# nuc5v1.net
KiCad netlist of a schematic drawn in Altium Designer
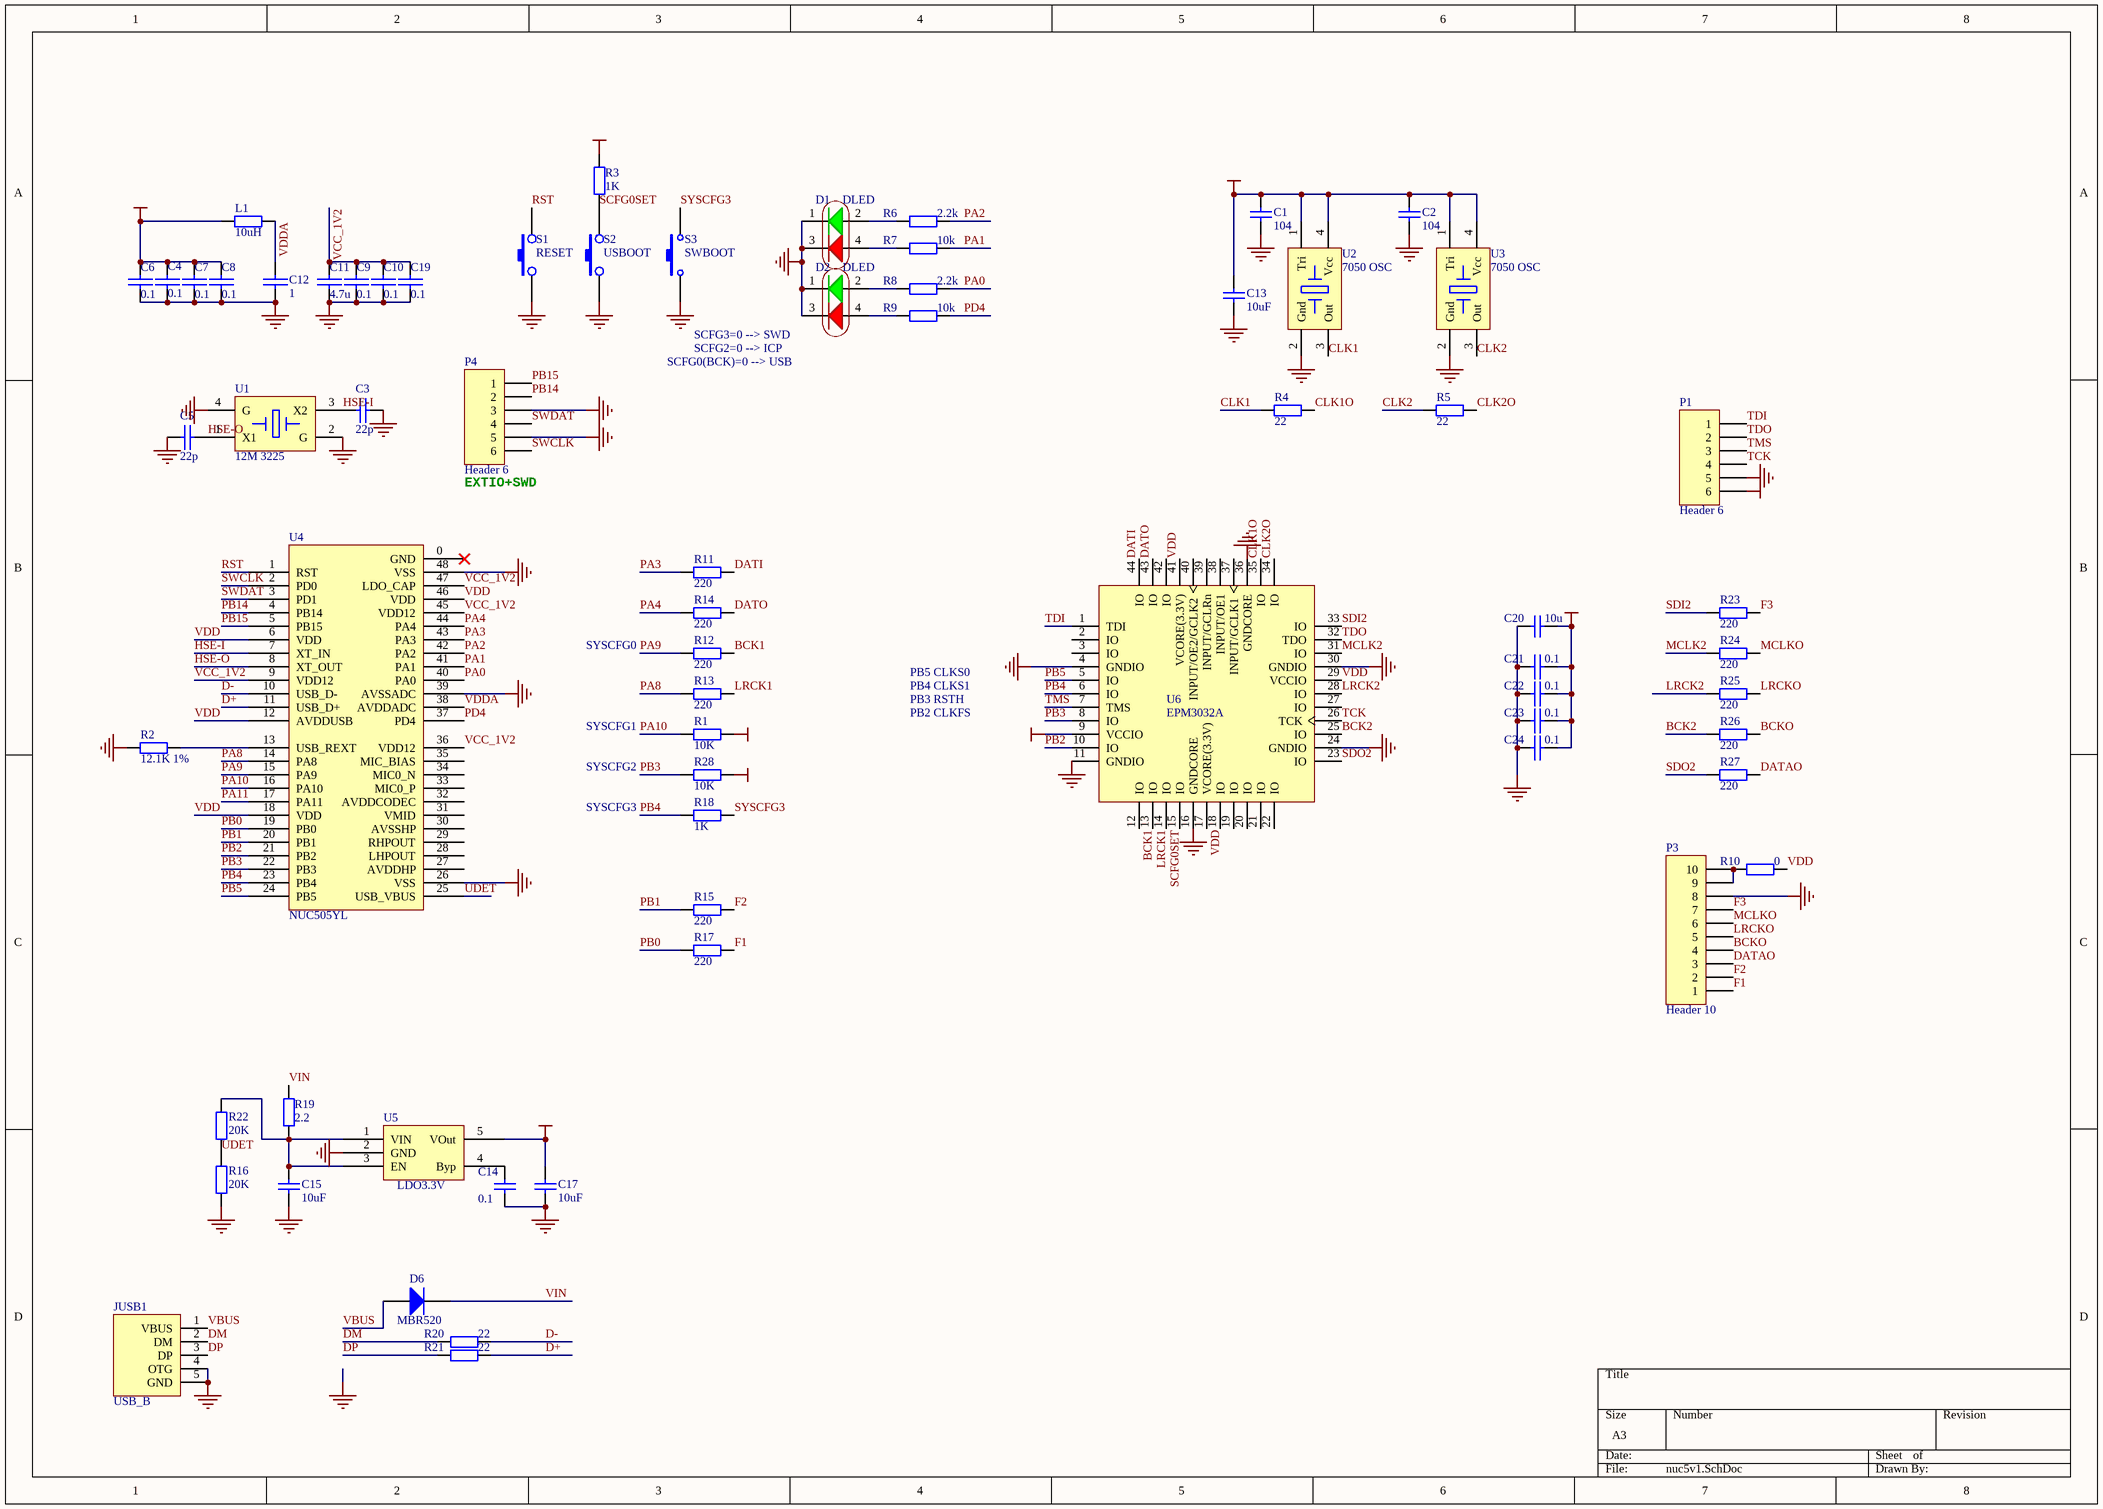
[diagram p0: nuc5v1.SchDoc]

(export (version "E")
  (design (tool "Eeschema 10.0.6"))
  (components
    (comp (ref "C1")
      (value "104")
      (footprint "CC0603CAP")
      (description "Capacitor0603")
      (libsource (lib "ADI1955-Sch") (part "Cap6"))
    )
    (comp (ref "C2")
      (value "104")
      (footprint "CC0603CAP")
      (description "Capacitor0603")
      (libsource (lib "ADI1955-Sch") (part "Cap6"))
    )
    (comp (ref "C3")
      (value "22p")
      (footprint "0603")
      (description "Capacitor")
      (libsource (lib "*") (part "CAP"))
    )
    (comp (ref "C4")
      (value "0.1")
      (footprint "0603")
      (description "Capacitor")
      (libsource (lib "*") (part "CAP"))
    )
    (comp (ref "C5")
      (value "22p")
      (footprint "0603")
      (description "Capacitor")
      (libsource (lib "") (part "CAP_1"))
    )
    (comp (ref "C6")
      (value "0.1")
      (footprint "0603")
      (description "Capacitor")
      (libsource (lib "*") (part "CAP"))
    )
    (comp (ref "C7")
      (value "0.1")
      (footprint "0603")
      (description "Capacitor")
      (libsource (lib "*") (part "CAP"))
    )
    (comp (ref "C8")
      (value "0.1")
      (footprint "0603")
      (description "Capacitor")
      (libsource (lib "*") (part "CAP"))
    )
    (comp (ref "C9")
      (value "0.1")
      (footprint "0603")
      (description "Capacitor")
      (libsource (lib "*") (part "CAP"))
    )
    (comp (ref "C10")
      (value "0.1")
      (footprint "0603")
      (description "Capacitor")
      (libsource (lib "*") (part "CAP"))
    )
    (comp (ref "C11")
      (value "4.7u")
      (footprint "0603")
      (description "Capacitor")
      (libsource (lib "*") (part "CAP"))
    )
    (comp (ref "C12")
      (value "1")
      (footprint "0603")
      (description "Capacitor")
      (libsource (lib "*") (part "CAP"))
    )
    (comp (ref "C13")
      (value "10uF")
      (footprint "CC0805CAP")
      (description "Capacitor0805")
      (libsource (lib "AudioLCR") (part "Cap8"))
    )
    (comp (ref "C14")
      (value "0.1")
      (footprint "0603")
      (description "Capacitor0805")
      (libsource (lib "*") (part "Cap8"))
    )
    (comp (ref "C15")
      (value "10uF")
      (footprint "CC0805CAP")
      (description "Capacitor0805")
      (libsource (lib "AudioLCR") (part "Cap8"))
    )
    (comp (ref "C17")
      (value "10uF")
      (footprint "CC0805CAP")
      (description "Capacitor0805")
      (libsource (lib "AudioLCR") (part "Cap8"))
    )
    (comp (ref "C19")
      (value "0.1")
      (footprint "0603")
      (description "Capacitor")
      (libsource (lib "*") (part "CAP"))
    )
    (comp (ref "C20")
      (value "10u")
      (footprint "CC0805CAP")
      (description "Capacitor0805")
      (libsource (lib "S1-LCR") (part "Cap8"))
    )
    (comp (ref "C21")
      (value "0.1")
      (footprint "0603")
      (description "Capacitor")
      (libsource (lib "*") (part "CAP"))
    )
    (comp (ref "C22")
      (value "0.1")
      (footprint "0603")
      (description "Capacitor")
      (libsource (lib "*") (part "CAP"))
    )
    (comp (ref "C23")
      (value "0.1")
      (footprint "0603")
      (description "Capacitor")
      (libsource (lib "*") (part "CAP"))
    )
    (comp (ref "C24")
      (value "0.1")
      (footprint "0603")
      (description "Capacitor")
      (libsource (lib "*") (part "CAP"))
    )
    (comp (ref "D1")
      (value "DLED")
      (footprint "LED1204")
      (description "1204双色LED")
      (libsource (lib "S1-常用") (part "LED1204"))
    )
    (comp (ref "D2")
      (value "DLED")
      (footprint "LED1204")
      (description "1204双色LED")
      (libsource (lib "S1-常用") (part "LED1204"))
    )
    (comp (ref "D6")
      (value "MBR520")
      (footprint "SOD123")
      (description "Default Diode")
      (libsource (lib "Miscellaneous Devices") (part "Diode"))
    )
    (comp (ref "JUSB1")
      (value "USB_B")
      (footprint "USB-B-M")
      (description "USB Mini/Micro 5P")
      (libsource (lib "AudioLCR") (part "USB_B"))
    )
    (comp (ref "L1")
      (value "10uH")
      (footprint "CC0805RES")
      (description "Resistor0805")
      (libsource (lib "ADI1955-Sch") (part "Res8"))
    )
    (comp (ref "P1")
      (value "Header 6")
      (footprint "密脚针1.27mm*6")
      (description "Header, 6-Pin")
      (fields (field (name "PUBLISHER") "Altium Limited"))
      (libsource (lib "Miscellaneous Connectors") (part "Header 6"))
    )
    (comp (ref "P3")
      (value "Header 10")
      (footprint "HDR1X10")
      (description "Header, 10-Pin")
      (fields (field (name "PUBLISHER") "Altium Limited"))
      (libsource (lib "Miscellaneous Connectors") (part "Header 10"))
    )
    (comp (ref "P4")
      (value "Header 6")
      (footprint "密脚针1.27mm*6")
      (description "Header, 6-Pin")
      (fields (field (name "PUBLISHER") "Altium Limited"))
      (libsource (lib "Miscellaneous Connectors") (part "Header 6"))
    )
    (comp (ref "R1")
      (value "10K")
      (footprint "CR1005-0402")
      (description "Resistor0603")
      (libsource (lib "") (part "Res6_1"))
    )
    (comp (ref "R2")
      (value "12.1K 1%")
      (footprint "CR1005-0402")
      (description "Resistor0603")
      (libsource (lib "S1-LCR") (part "Res6"))
    )
    (comp (ref "R3")
      (value "1K")
      (footprint "CR1005-0402")
      (description "Resistor0603")
      (libsource (lib "*") (part "Res6"))
    )
    (comp (ref "R4")
      (value "22")
      (footprint "CR1005-0402")
      (description "Resistor0603")
      (libsource (lib "") (part "Res6_1"))
    )
    (comp (ref "R5")
      (value "22")
      (footprint "CR1005-0402")
      (description "Resistor0603")
      (libsource (lib "") (part "Res6_1"))
    )
    (comp (ref "R6")
      (value "2.2k")
      (footprint "CR1005-0402")
      (description "Resistor0603")
      (libsource (lib "ADI1955-Sch") (part "Res6"))
    )
    (comp (ref "R7")
      (value "10k")
      (footprint "CR1005-0402")
      (description "Resistor0603")
      (libsource (lib "ADI1955-Sch") (part "Res6"))
    )
    (comp (ref "R8")
      (value "2.2k")
      (footprint "CR1005-0402")
      (description "Resistor0603")
      (libsource (lib "ADI1955-Sch") (part "Res6"))
    )
    (comp (ref "R9")
      (value "10k")
      (footprint "CR1005-0402")
      (description "Resistor0603")
      (libsource (lib "ADI1955-Sch") (part "Res6"))
    )
    (comp (ref "R10")
      (value "0")
      (footprint "0603")
      (description "Resistor0603")
      (libsource (lib "ADI1955-Sch") (part "Res6"))
    )
    (comp (ref "R11")
      (value "220")
      (footprint "CR1005-0402")
      (description "Resistor0603")
      (libsource (lib "") (part "Res6_1"))
    )
    (comp (ref "R12")
      (value "220")
      (footprint "CR1005-0402")
      (description "Resistor0603")
      (libsource (lib "") (part "Res6_2"))
    )
    (comp (ref "R13")
      (value "220")
      (footprint "CR1005-0402")
      (description "Resistor0603")
      (libsource (lib "") (part "Res6_1"))
    )
    (comp (ref "R14")
      (value "220")
      (footprint "CR1005-0402")
      (description "Resistor0603")
      (libsource (lib "ADI1955-Sch") (part "Res6"))
    )
    (comp (ref "R15")
      (value "220")
      (footprint "CR1005-0402")
      (description "Resistor0603")
      (libsource (lib "ADI1955-Sch") (part "Res6"))
    )
    (comp (ref "R16")
      (value "20K")
      (footprint "CR1005-0402")
      (description "贴片电阻")
      (libsource (lib "MY LIB") (part "R"))
    )
    (comp (ref "R17")
      (value "220")
      (footprint "CR1005-0402")
      (description "Resistor0603")
      (libsource (lib "ADI1955-Sch") (part "Res6"))
    )
    (comp (ref "R18")
      (value "1K")
      (footprint "CR1005-0402")
      (description "Resistor0603")
      (libsource (lib "") (part "Res6_1"))
    )
    (comp (ref "R19")
      (value "2.2")
      (footprint "CC0603RES")
      (description "Resistor0603")
      (libsource (lib "AudioLCR") (part "Res6"))
    )
    (comp (ref "R20")
      (value "22")
      (footprint "CR1005-0402")
      (description "Resistor0603")
      (libsource (lib "ADI1955-Sch") (part "Res6"))
    )
    (comp (ref "R21")
      (value "22")
      (footprint "CR1005-0402")
      (description "Resistor0603")
      (libsource (lib "ADI1955-Sch") (part "Res6"))
    )
    (comp (ref "R22")
      (value "20K")
      (footprint "CR1005-0402")
      (description "贴片电阻")
      (libsource (lib "MY LIB") (part "R"))
    )
    (comp (ref "R23")
      (value "220")
      (footprint "CR1005-0402")
      (description "Resistor0603")
      (libsource (lib "") (part "Res6_1"))
    )
    (comp (ref "R24")
      (value "220")
      (footprint "CR1005-0402")
      (description "Resistor0603")
      (libsource (lib "ADI1955-Sch") (part "Res6"))
    )
    (comp (ref "R25")
      (value "220")
      (footprint "CR1005-0402")
      (description "Resistor0603")
      (libsource (lib "") (part "Res6_2"))
    )
    (comp (ref "R26")
      (value "220")
      (footprint "CR1005-0402")
      (description "Resistor0603")
      (libsource (lib "") (part "Res6_1"))
    )
    (comp (ref "R27")
      (value "220")
      (footprint "CR1005-0402")
      (description "Resistor0603")
      (libsource (lib "") (part "Res6_1"))
    )
    (comp (ref "R28")
      (value "10K")
      (footprint "CR1005-0402")
      (description "Resistor0603")
      (libsource (lib "") (part "Res6_1"))
    )
    (comp (ref "S1") (value "RESET") (footprint "密脚针1.27mm*2") (libsource (lib "*") (part "SW-PB")))
    (comp (ref "S2") (value "USBOOT") (footprint "密脚针1.27mm*2") (libsource (lib "*") (part "SW-PB")))
    (comp (ref "S3")
      (value "SWBOOT")
      (footprint "密脚针1.27mm*2")
      (description "Switch")
      (fields (field (name "PUBLISHER") "Altium Limited"))
      (libsource (lib "Miscellaneous Devices") (part "SW-PB"))
    )
    (comp (ref "U1") (value "12M 3225") (footprint "OSC-3225") (libsource (lib "AudioLCR") (part "XTAL")))
    (comp (ref "U2") (value "7050 OSC") (footprint "OSC-3225") (libsource (lib "AudioLCR") (part "XTAL_OSC")))
    (comp (ref "U3") (value "7050 OSC") (footprint "OSC-3225") (libsource (lib "AudioLCR") (part "XTAL_OSC")))
    (comp (ref "U4") (value "NUC505YL") (footprint "LQFP-48") (libsource (lib "NUC505YL") (part "NUC505YL")))
    (comp (ref "U5")
      (value "LDO3.3V")
      (footprint "SOT23-5")
      (description "LP2985 5V LDO")
      (libsource (lib "ADI1955-Sch") (part "LP2985-5"))
    )
    (comp (ref "U6")
      (value "EPM3032A")
      (footprint "TQFP44")
      (description "CPLD , 44-Pin TQFP")
      (libsource (lib "Altera MAX 3000A") (part "EPM3032A"))
    )
  )
  (nets
    (net (code "1") (name "/BCK1") (class "Default")
      (node (ref "R12") (pin "1") (pinfunction "1_1") (pintype "passive"))
      (node (ref "U6") (pin "12") (pinfunction "IO_12") (pintype "passive"))
    )
    (net (code "2") (name "/BCK2") (class "Default")
      (node (ref "R26") (pin "1") (pinfunction "1_1") (pintype "passive"))
      (node (ref "U6") (pin "25") (pinfunction "IO_25") (pintype "passive"))
    )
    (net (code "3") (name "/BCKO") (class "Default")
      (node (ref "P3") (pin "4") (pinfunction "4_4") (pintype "passive"))
      (node (ref "R26") (pin "2") (pinfunction "2_2") (pintype "passive"))
    )
    (net (code "4") (name "/CLK1") (class "Default")
      (node (ref "R4") (pin "1") (pinfunction "1_1") (pintype "passive"))
      (node (ref "U2") (pin "3") (pinfunction "Out_3") (pintype "passive"))
    )
    (net (code "5") (name "/CLK1O") (class "Default")
      (node (ref "R4") (pin "2") (pinfunction "2_2") (pintype "passive"))
      (node (ref "U6") (pin "35") (pinfunction "IO_35") (pintype "passive"))
    )
    (net (code "6") (name "/CLK2") (class "Default")
      (node (ref "R5") (pin "1") (pinfunction "1_1") (pintype "passive"))
      (node (ref "U3") (pin "3") (pinfunction "Out_3") (pintype "passive"))
    )
    (net (code "7") (name "/CLK2O") (class "Default")
      (node (ref "R5") (pin "2") (pinfunction "2_2") (pintype "passive"))
      (node (ref "U6") (pin "34") (pinfunction "IO_34") (pintype "passive"))
    )
    (net (code "8") (name "/D+") (class "Default")
      (node (ref "R21") (pin "1") (pinfunction "1_1") (pintype "passive"))
      (node (ref "U4") (pin "11") (pinfunction "USB_D+_11") (pintype "passive"))
    )
    (net (code "9") (name "/D-") (class "Default")
      (node (ref "R20") (pin "1") (pinfunction "1_1") (pintype "passive"))
      (node (ref "U4") (pin "10") (pinfunction "USB_D-_10") (pintype "passive"))
    )
    (net (code "10") (name "/DATAO") (class "Default")
      (node (ref "P3") (pin "3") (pinfunction "3_3") (pintype "passive"))
      (node (ref "R27") (pin "2") (pinfunction "2_2") (pintype "passive"))
    )
    (net (code "11") (name "/DATI") (class "Default")
      (node (ref "R11") (pin "2") (pinfunction "2_2") (pintype "passive"))
      (node (ref "U6") (pin "44") (pinfunction "IO_44") (pintype "passive"))
    )
    (net (code "12") (name "/DATO") (class "Default")
      (node (ref "R14") (pin "1") (pinfunction "1_1") (pintype "passive"))
      (node (ref "U6") (pin "43") (pinfunction "IO_43") (pintype "passive"))
    )
    (net (code "13") (name "/DM") (class "Default")
      (node (ref "JUSB1") (pin "2") (pinfunction "DM_2") (pintype "passive"))
      (node (ref "R20") (pin "2") (pinfunction "2_2") (pintype "passive"))
    )
    (net (code "14") (name "/DP") (class "Default")
      (node (ref "JUSB1") (pin "3") (pinfunction "DP_3") (pintype "passive"))
      (node (ref "R21") (pin "2") (pinfunction "2_2") (pintype "passive"))
    )
    (net (code "15") (name "/F1") (class "Default")
      (node (ref "P3") (pin "1") (pinfunction "1_1") (pintype "passive"))
      (node (ref "R17") (pin "1") (pinfunction "1_1") (pintype "passive"))
    )
    (net (code "16") (name "/F2") (class "Default")
      (node (ref "P3") (pin "2") (pinfunction "2_2") (pintype "passive"))
      (node (ref "R15") (pin "1") (pinfunction "1_1") (pintype "passive"))
    )
    (net (code "17") (name "/F3") (class "Default")
      (node (ref "P3") (pin "7") (pinfunction "7_7") (pintype "passive"))
      (node (ref "R23") (pin "2") (pinfunction "2_2") (pintype "passive"))
    )
    (net (code "18") (name "/HSE-I") (class "Default")
      (node (ref "C3") (pin "1") (pinfunction "1_1") (pintype "passive"))
      (node (ref "U1") (pin "3") (pinfunction "X2_3") (pintype "passive"))
      (node (ref "U4") (pin "7") (pinfunction "XT_IN_7") (pintype "passive"))
    )
    (net (code "19") (name "/HSE-O") (class "Default")
      (node (ref "C5") (pin "2") (pinfunction "2_2") (pintype "passive"))
      (node (ref "U1") (pin "1") (pinfunction "X1_1") (pintype "passive"))
      (node (ref "U4") (pin "8") (pinfunction "XT_OUT_8") (pintype "passive"))
    )
    (net (code "20") (name "/LRCK1") (class "Default")
      (node (ref "R13") (pin "2") (pinfunction "2_2") (pintype "passive"))
      (node (ref "U6") (pin "13") (pinfunction "IO_13") (pintype "passive"))
    )
    (net (code "21") (name "/LRCK2") (class "Default")
      (node (ref "R25") (pin "2") (pinfunction "2_2") (pintype "passive"))
      (node (ref "U6") (pin "28") (pinfunction "IO_28") (pintype "passive"))
    )
    (net (code "22") (name "/LRCKO") (class "Default")
      (node (ref "P3") (pin "5") (pinfunction "5_5") (pintype "passive"))
      (node (ref "R25") (pin "1") (pinfunction "1_1") (pintype "passive"))
    )
    (net (code "23") (name "/MCLK2") (class "Default")
      (node (ref "R24") (pin "2") (pinfunction "2_2") (pintype "passive"))
      (node (ref "U6") (pin "31") (pinfunction "IO_31") (pintype "passive"))
    )
    (net (code "24") (name "/MCLKO") (class "Default")
      (node (ref "P3") (pin "6") (pinfunction "6_6") (pintype "passive"))
      (node (ref "R24") (pin "1") (pinfunction "1_1") (pintype "passive"))
    )
    (net (code "25") (name "/PA0") (class "Default")
      (node (ref "R8") (pin "1") (pinfunction "1_1") (pintype "passive"))
      (node (ref "U4") (pin "40") (pinfunction "PA0_40") (pintype "passive"))
    )
    (net (code "26") (name "/PA1") (class "Default")
      (node (ref "R7") (pin "1") (pinfunction "1_1") (pintype "passive"))
      (node (ref "U4") (pin "41") (pinfunction "PA1_41") (pintype "passive"))
    )
    (net (code "27") (name "/PA2") (class "Default")
      (node (ref "R6") (pin "1") (pinfunction "1_1") (pintype "passive"))
      (node (ref "U4") (pin "42") (pinfunction "PA2_42") (pintype "passive"))
    )
    (net (code "28") (name "/PA3") (class "Default")
      (node (ref "R11") (pin "1") (pinfunction "1_1") (pintype "passive"))
      (node (ref "U4") (pin "43") (pinfunction "PA3_43") (pintype "passive"))
    )
    (net (code "29") (name "/PA4") (class "Default")
      (node (ref "R14") (pin "2") (pinfunction "2_2") (pintype "passive"))
      (node (ref "U4") (pin "44") (pinfunction "PA4_44") (pintype "passive"))
    )
    (net (code "30") (name "/PA8") (class "Default")
      (node (ref "R13") (pin "1") (pinfunction "1_1") (pintype "passive"))
      (node (ref "U4") (pin "14") (pinfunction "PA8_14") (pintype "passive"))
    )
    (net (code "31") (name "/PA9") (class "Default")
      (node (ref "R12") (pin "2") (pinfunction "2_2") (pintype "passive"))
      (node (ref "U4") (pin "15") (pinfunction "PA9_15") (pintype "passive"))
    )
    (net (code "32") (name "/PA10") (class "Default")
      (node (ref "R1") (pin "1") (pinfunction "1_1") (pintype "passive"))
      (node (ref "U4") (pin "16") (pinfunction "PA10_16") (pintype "passive"))
    )
    (net (code "33") (name "/PA11") (class "Default")
      (node (ref "U4") (pin "17") (pinfunction "PA11_17") (pintype "passive"))
    )
    (net (code "34") (name "/PB0") (class "Default")
      (node (ref "R17") (pin "2") (pinfunction "2_2") (pintype "passive"))
      (node (ref "U4") (pin "19") (pinfunction "PB0_19") (pintype "passive"))
    )
    (net (code "35") (name "/PB1") (class "Default")
      (node (ref "R15") (pin "2") (pinfunction "2_2") (pintype "passive"))
      (node (ref "U4") (pin "20") (pinfunction "PB1_20") (pintype "passive"))
    )
    (net (code "36") (name "/PB2") (class "Default")
      (node (ref "U4") (pin "21") (pinfunction "PB2_21") (pintype "passive"))
      (node (ref "U6") (pin "10") (pinfunction "IO_10") (pintype "passive"))
    )
    (net (code "37") (name "/PB3") (class "Default")
      (node (ref "R28") (pin "1") (pinfunction "1_1") (pintype "passive"))
      (node (ref "U4") (pin "22") (pinfunction "PB3_22") (pintype "passive"))
      (node (ref "U6") (pin "8") (pinfunction "IO_8") (pintype "passive"))
    )
    (net (code "38") (name "/PB4") (class "Default")
      (node (ref "R18") (pin "1") (pinfunction "1_1") (pintype "passive"))
      (node (ref "U4") (pin "23") (pinfunction "PB4_23") (pintype "passive"))
      (node (ref "U6") (pin "6") (pinfunction "IO_6") (pintype "passive"))
    )
    (net (code "39") (name "/PB5") (class "Default")
      (node (ref "U4") (pin "24") (pinfunction "PB5_24") (pintype "passive"))
      (node (ref "U6") (pin "5") (pinfunction "IO_5") (pintype "passive"))
    )
    (net (code "40") (name "/PB14") (class "Default")
      (node (ref "P4") (pin "2") (pinfunction "2_2") (pintype "passive"))
      (node (ref "U4") (pin "4") (pinfunction "PB14_4") (pintype "passive"))
    )
    (net (code "41") (name "/PB15") (class "Default")
      (node (ref "P4") (pin "1") (pinfunction "1_1") (pintype "passive"))
      (node (ref "U4") (pin "5") (pinfunction "PB15_5") (pintype "passive"))
    )
    (net (code "42") (name "/PD4") (class "Default")
      (node (ref "R9") (pin "1") (pinfunction "1_1") (pintype "passive"))
      (node (ref "U4") (pin "37") (pinfunction "PD4_37") (pintype "passive"))
    )
    (net (code "43") (name "/RST") (class "Default")
      (node (ref "S1") (pin "2") (pinfunction "2_2") (pintype "passive"))
      (node (ref "U4") (pin "1") (pinfunction "RST_1") (pintype "passive"))
    )
    (net (code "44") (name "/SCFG0SET") (class "Default")
      (node (ref "R3") (pin "1") (pinfunction "1_1") (pintype "passive"))
      (node (ref "S2") (pin "2") (pinfunction "2_2") (pintype "passive"))
      (node (ref "U6") (pin "14") (pinfunction "IO_14") (pintype "passive"))
    )
    (net (code "45") (name "/SDI2") (class "Default")
      (node (ref "R23") (pin "1") (pinfunction "1_1") (pintype "passive"))
      (node (ref "U6") (pin "33") (pinfunction "IO_33") (pintype "passive"))
    )
    (net (code "46") (name "/SDO2") (class "Default")
      (node (ref "R27") (pin "1") (pinfunction "1_1") (pintype "passive"))
      (node (ref "U6") (pin "23") (pinfunction "IO_23") (pintype "passive"))
    )
    (net (code "47") (name "/SWCLK") (class "Default")
      (node (ref "P4") (pin "6") (pinfunction "6_6") (pintype "passive"))
      (node (ref "U4") (pin "2") (pinfunction "PD0_2") (pintype "passive"))
    )
    (net (code "48") (name "/SWDAT") (class "Default")
      (node (ref "P4") (pin "4") (pinfunction "4_4") (pintype "passive"))
      (node (ref "U4") (pin "3") (pinfunction "PD1_3") (pintype "passive"))
    )
    (net (code "49") (name "/SYSCFG3") (class "Default")
      (node (ref "R18") (pin "2") (pinfunction "2_2") (pintype "passive"))
      (node (ref "S3") (pin "2") (pinfunction "2_2") (pintype "passive"))
    )
    (net (code "50") (name "/TCK") (class "Default")
      (node (ref "P1") (pin "4") (pinfunction "4_4") (pintype "passive"))
      (node (ref "U6") (pin "26") (pinfunction "TCK_26") (pintype "passive"))
    )
    (net (code "51") (name "/TDI") (class "Default")
      (node (ref "P1") (pin "1") (pinfunction "1_1") (pintype "passive"))
      (node (ref "U6") (pin "1") (pinfunction "TDI_1") (pintype "passive"))
    )
    (net (code "52") (name "/TDO") (class "Default")
      (node (ref "P1") (pin "2") (pinfunction "2_2") (pintype "passive"))
      (node (ref "U6") (pin "32") (pinfunction "TDO_32") (pintype "passive"))
    )
    (net (code "53") (name "/TMS") (class "Default")
      (node (ref "P1") (pin "3") (pinfunction "3_3") (pintype "passive"))
      (node (ref "U6") (pin "7") (pinfunction "TMS_7") (pintype "passive"))
    )
    (net (code "54") (name "/UDET") (class "Default")
      (node (ref "R16") (pin "2") (pinfunction "2_2") (pintype "passive"))
      (node (ref "R22") (pin "1") (pinfunction "1_1") (pintype "passive"))
      (node (ref "U4") (pin "25") (pinfunction "USB_VBUS_25") (pintype "passive"))
    )
    (net (code "55") (name "/VBUS") (class "Default")
      (node (ref "D6") (pin "1") (pinfunction "A_1") (pintype "passive"))
      (node (ref "JUSB1") (pin "1") (pinfunction "VBUS_1") (pintype "passive"))
    )
    (net (code "56") (name "/VCC_1V2") (class "Default")
      (node (ref "C10") (pin "1") (pinfunction "1_1") (pintype "passive"))
      (node (ref "C11") (pin "1") (pinfunction "1_1") (pintype "passive"))
      (node (ref "C19") (pin "1") (pinfunction "1_1") (pintype "passive"))
      (node (ref "C9") (pin "1") (pinfunction "1_1") (pintype "passive"))
      (node (ref "U4") (pin "36") (pinfunction "VDD12_36") (pintype "passive"))
      (node (ref "U4") (pin "45") (pinfunction "VDD12_45") (pintype "passive"))
      (node (ref "U4") (pin "47") (pinfunction "LDO_CAP_47") (pintype "passive"))
      (node (ref "U4") (pin "9") (pinfunction "VDD12_9") (pintype "passive"))
    )
    (net (code "57") (name "/VDDA") (class "Default")
      (node (ref "C12") (pin "1") (pinfunction "1_1") (pintype "passive"))
      (node (ref "L1") (pin "2") (pinfunction "2_2") (pintype "passive"))
      (node (ref "U4") (pin "38") (pinfunction "AVDDADC_38") (pintype "passive"))
    )
    (net (code "58") (name "/VIN") (class "Default")
      (node (ref "D6") (pin "2") (pinfunction "K_2") (pintype "passive"))
      (node (ref "R19") (pin "1") (pinfunction "1_1") (pintype "passive"))
    )
    (net (code "59") (name "GND") (class "Default")
      (node (ref "C1") (pin "1") (pinfunction "1_1") (pintype "passive"))
      (node (ref "C10") (pin "2") (pinfunction "2_2") (pintype "passive"))
      (node (ref "C11") (pin "2") (pinfunction "2_2") (pintype "passive"))
      (node (ref "C12") (pin "2") (pinfunction "2_2") (pintype "passive"))
      (node (ref "C13") (pin "1") (pinfunction "1_1") (pintype "passive"))
      (node (ref "C14") (pin "2") (pinfunction "2_2") (pintype "passive"))
      (node (ref "C15") (pin "1") (pinfunction "1_1") (pintype "passive"))
      (node (ref "C17") (pin "1") (pinfunction "1_1") (pintype "passive"))
      (node (ref "C19") (pin "2") (pinfunction "2_2") (pintype "passive"))
      (node (ref "C2") (pin "2") (pinfunction "2_2") (pintype "passive"))
      (node (ref "C20") (pin "2") (pinfunction "2_2") (pintype "passive"))
      (node (ref "C21") (pin "1") (pinfunction "1_1") (pintype "passive"))
      (node (ref "C22") (pin "1") (pinfunction "1_1") (pintype "passive"))
      (node (ref "C23") (pin "1") (pinfunction "1_1") (pintype "passive"))
      (node (ref "C24") (pin "1") (pinfunction "1_1") (pintype "passive"))
      (node (ref "C3") (pin "2") (pinfunction "2_2") (pintype "passive"))
      (node (ref "C4") (pin "2") (pinfunction "2_2") (pintype "passive"))
      (node (ref "C5") (pin "1") (pinfunction "1_1") (pintype "passive"))
      (node (ref "C6") (pin "2") (pinfunction "2_2") (pintype "passive"))
      (node (ref "C7") (pin "1") (pinfunction "1_1") (pintype "passive"))
      (node (ref "C8") (pin "2") (pinfunction "2_2") (pintype "passive"))
      (node (ref "C9") (pin "2") (pinfunction "2_2") (pintype "passive"))
      (node (ref "D1") (pin "1") (pinfunction "1_1") (pintype "passive"))
      (node (ref "D1") (pin "3") (pinfunction "3_3") (pintype "passive"))
      (node (ref "D2") (pin "1") (pinfunction "1_1") (pintype "passive"))
      (node (ref "D2") (pin "3") (pinfunction "3_3") (pintype "passive"))
      (node (ref "JUSB1") (pin "4") (pinfunction "OTG_4") (pintype "passive"))
      (node (ref "JUSB1") (pin "5") (pinfunction "GND_5") (pintype "passive"))
      (node (ref "P1") (pin "5") (pinfunction "5_5") (pintype "passive"))
      (node (ref "P3") (pin "8") (pinfunction "8_8") (pintype "passive"))
      (node (ref "P4") (pin "3") (pinfunction "3_3") (pintype "passive"))
      (node (ref "P4") (pin "5") (pinfunction "5_5") (pintype "passive"))
      (node (ref "R16") (pin "1") (pinfunction "1_1") (pintype "passive"))
      (node (ref "R2") (pin "2") (pinfunction "2_2") (pintype "passive"))
      (node (ref "S1") (pin "1") (pinfunction "1_1") (pintype "passive"))
      (node (ref "S2") (pin "1") (pinfunction "1_1") (pintype "passive"))
      (node (ref "S3") (pin "1") (pinfunction "1_1") (pintype "passive"))
      (node (ref "U1") (pin "2") (pinfunction "G_2") (pintype "passive"))
      (node (ref "U1") (pin "4") (pinfunction "G_4") (pintype "passive"))
      (node (ref "U2") (pin "2") (pinfunction "Gnd_2") (pintype "passive"))
      (node (ref "U3") (pin "2") (pinfunction "Gnd_2") (pintype "passive"))
      (node (ref "U4") (pin "26") (pinfunction "VSS_26") (pintype "passive"))
      (node (ref "U4") (pin "39") (pinfunction "AVSSADC_39") (pintype "passive"))
      (node (ref "U4") (pin "48") (pinfunction "VSS_48") (pintype "passive"))
      (node (ref "U5") (pin "2") (pinfunction "GND_2") (pintype "passive"))
      (node (ref "U6") (pin "11") (pinfunction "GNDIO_11") (pintype "passive"))
      (node (ref "U6") (pin "16") (pinfunction "GNDCORE_16") (pintype "passive"))
      (node (ref "U6") (pin "24") (pinfunction "GNDIO_24") (pintype "passive"))
      (node (ref "U6") (pin "30") (pinfunction "GNDIO_30") (pintype "passive"))
      (node (ref "U6") (pin "36") (pinfunction "GNDCORE_36") (pintype "passive"))
      (node (ref "U6") (pin "4") (pinfunction "GNDIO_4") (pintype "passive"))
    )
    (net (code "60") (name "Net-(D1-Pad2)") (class "Default")
      (node (ref "D1") (pin "2") (pinfunction "2_2") (pintype "passive"))
      (node (ref "R6") (pin "2") (pinfunction "2_2") (pintype "passive"))
    )
    (net (code "61") (name "Net-(D1-Pad4)") (class "Default")
      (node (ref "D1") (pin "4") (pinfunction "4_4") (pintype "passive"))
      (node (ref "R7") (pin "2") (pinfunction "2_2") (pintype "passive"))
    )
    (net (code "62") (name "Net-(D2-Pad2)") (class "Default")
      (node (ref "D2") (pin "2") (pinfunction "2_2") (pintype "passive"))
      (node (ref "R8") (pin "2") (pinfunction "2_2") (pintype "passive"))
    )
    (net (code "63") (name "Net-(D2-Pad4)") (class "Default")
      (node (ref "D2") (pin "4") (pinfunction "4_4") (pintype "passive"))
      (node (ref "R9") (pin "2") (pinfunction "2_2") (pintype "passive"))
    )
    (net (code "64") (name "Net-(P3-Pad10)") (class "Default")
      (node (ref "P3") (pin "10") (pinfunction "10_10") (pintype "passive"))
      (node (ref "P3") (pin "9") (pinfunction "9_9") (pintype "passive"))
      (node (ref "R10") (pin "2") (pinfunction "2_2") (pintype "passive"))
    )
    (net (code "65") (name "Net-(U4-USB_REXT)") (class "Default")
      (node (ref "R2") (pin "1") (pinfunction "1_1") (pintype "passive"))
      (node (ref "U4") (pin "13") (pinfunction "USB_REXT_13") (pintype "passive"))
    )
    (net (code "66") (name "Net-(U5-Byp)") (class "Default")
      (node (ref "C14") (pin "1") (pinfunction "1_1") (pintype "passive"))
      (node (ref "U5") (pin "4") (pinfunction "Byp_4") (pintype "passive"))
    )
    (net (code "67") (name "Net-(U5-EN)") (class "Default")
      (node (ref "C15") (pin "2") (pinfunction "2_2") (pintype "passive"))
      (node (ref "R19") (pin "2") (pinfunction "2_2") (pintype "passive"))
      (node (ref "R22") (pin "2") (pinfunction "2_2") (pintype "passive"))
      (node (ref "U5") (pin "1") (pinfunction "VIN_1") (pintype "passive"))
      (node (ref "U5") (pin "3") (pinfunction "EN_3") (pintype "passive"))
    )
    (net (code "68") (name "VDD") (class "Default")
      (node (ref "C1") (pin "2") (pinfunction "2_2") (pintype "passive"))
      (node (ref "C13") (pin "2") (pinfunction "2_2") (pintype "passive"))
      (node (ref "C17") (pin "2") (pinfunction "2_2") (pintype "passive"))
      (node (ref "C2") (pin "1") (pinfunction "1_1") (pintype "passive"))
      (node (ref "C20") (pin "1") (pinfunction "1_1") (pintype "passive"))
      (node (ref "C21") (pin "2") (pinfunction "2_2") (pintype "passive"))
      (node (ref "C22") (pin "2") (pinfunction "2_2") (pintype "passive"))
      (node (ref "C23") (pin "2") (pinfunction "2_2") (pintype "passive"))
      (node (ref "C24") (pin "2") (pinfunction "2_2") (pintype "passive"))
      (node (ref "C4") (pin "1") (pinfunction "1_1") (pintype "passive"))
      (node (ref "C6") (pin "1") (pinfunction "1_1") (pintype "passive"))
      (node (ref "C7") (pin "2") (pinfunction "2_2") (pintype "passive"))
      (node (ref "C8") (pin "1") (pinfunction "1_1") (pintype "passive"))
      (node (ref "L1") (pin "1") (pinfunction "1_1") (pintype "passive"))
      (node (ref "P1") (pin "6") (pinfunction "6_6") (pintype "passive"))
      (node (ref "R1") (pin "2") (pinfunction "2_2") (pintype "passive"))
      (node (ref "R10") (pin "1") (pinfunction "1_1") (pintype "passive"))
      (node (ref "R28") (pin "2") (pinfunction "2_2") (pintype "passive"))
      (node (ref "R3") (pin "2") (pinfunction "2_2") (pintype "passive"))
      (node (ref "U2") (pin "1") (pinfunction "Tri_1") (pintype "passive"))
      (node (ref "U2") (pin "4") (pinfunction "Vcc_4") (pintype "passive"))
      (node (ref "U3") (pin "1") (pinfunction "Tri_1") (pintype "passive"))
      (node (ref "U3") (pin "4") (pinfunction "Vcc_4") (pintype "passive"))
      (node (ref "U4") (pin "12") (pinfunction "AVDDUSB_12") (pintype "passive"))
      (node (ref "U4") (pin "18") (pinfunction "VDD_18") (pintype "passive"))
      (node (ref "U4") (pin "46") (pinfunction "VDD_46") (pintype "passive"))
      (node (ref "U4") (pin "6") (pinfunction "VDD_6") (pintype "passive"))
      (node (ref "U5") (pin "5") (pinfunction "VOut_5") (pintype "passive"))
      (node (ref "U6") (pin "17") (pinfunction "VCORE(3.3V)_17") (pintype "passive"))
      (node (ref "U6") (pin "29") (pinfunction "VCCIO_29") (pintype "passive"))
      (node (ref "U6") (pin "41") (pinfunction "VCORE(3.3V)_41") (pintype "passive"))
      (node (ref "U6") (pin "9") (pinfunction "VCCIO_9") (pintype "passive"))
    )
    (net (code "69") (name "unconnected-(U4-AVDDCODEC-Pad32)") (class "Default")
      (node (ref "U4") (pin "32") (pinfunction "AVDDCODEC_32") (pintype "passive"))
    )
    (net (code "70") (name "unconnected-(U4-AVDDHP-Pad27)") (class "Default")
      (node (ref "U4") (pin "27") (pinfunction "AVDDHP_27") (pintype "passive"))
    )
    (net (code "71") (name "unconnected-(U4-AVSSHP-Pad30)") (class "Default")
      (node (ref "U4") (pin "30") (pinfunction "AVSSHP_30") (pintype "passive"))
    )
    (net (code "72") (name "unconnected-(U4-GND-Pad0)") (class "Default")
      (node (ref "U4") (pin "0") (pinfunction "GND_0") (pintype "passive+no_connect"))
    )
    (net (code "73") (name "unconnected-(U4-LHPOUT-Pad28)") (class "Default")
      (node (ref "U4") (pin "28") (pinfunction "LHPOUT_28") (pintype "passive"))
    )
    (net (code "74") (name "unconnected-(U4-MIC0_N-Pad34)") (class "Default")
      (node (ref "U4") (pin "34") (pinfunction "MIC0_N_34") (pintype "passive"))
    )
    (net (code "75") (name "unconnected-(U4-MIC0_P-Pad33)") (class "Default")
      (node (ref "U4") (pin "33") (pinfunction "MIC0_P_33") (pintype "passive"))
    )
    (net (code "76") (name "unconnected-(U4-MIC_BIAS-Pad35)") (class "Default")
      (node (ref "U4") (pin "35") (pinfunction "MIC_BIAS_35") (pintype "passive"))
    )
    (net (code "77") (name "unconnected-(U4-RHPOUT-Pad29)") (class "Default")
      (node (ref "U4") (pin "29") (pinfunction "RHPOUT_29") (pintype "passive"))
    )
    (net (code "78") (name "unconnected-(U4-VMID-Pad31)") (class "Default")
      (node (ref "U4") (pin "31") (pinfunction "VMID_31") (pintype "passive"))
    )
    (net (code "79") (name "unconnected-(U6-INPUT{slash}GCLK1-Pad37)") (class "Default")
      (node (ref "U6") (pin "37") (pinfunction "INPUT/GCLK1_37") (pintype "passive"))
    )
    (net (code "80") (name "unconnected-(U6-INPUT{slash}GCLRn-Pad39)") (class "Default")
      (node (ref "U6") (pin "39") (pinfunction "INPUT/GCLRn_39") (pintype "passive"))
    )
    (net (code "81") (name "unconnected-(U6-INPUT{slash}OE1-Pad38)") (class "Default")
      (node (ref "U6") (pin "38") (pinfunction "INPUT/OE1_38") (pintype "passive"))
    )
    (net (code "82") (name "unconnected-(U6-INPUT{slash}OE2{slash}GCLK2-Pad40)") (class "Default")
      (node (ref "U6") (pin "40") (pinfunction "INPUT/OE2/GCLK2_40") (pintype "passive"))
    )
    (net (code "83") (name "unconnected-(U6-IO-Pad2)") (class "Default")
      (node (ref "U6") (pin "2") (pinfunction "IO_2") (pintype "passive"))
    )
    (net (code "84") (name "unconnected-(U6-IO-Pad3)") (class "Default")
      (node (ref "U6") (pin "3") (pinfunction "IO_3") (pintype "passive"))
    )
    (net (code "85") (name "unconnected-(U6-IO-Pad15)") (class "Default")
      (node (ref "U6") (pin "15") (pinfunction "IO_15") (pintype "passive"))
    )
    (net (code "86") (name "unconnected-(U6-IO-Pad18)") (class "Default")
      (node (ref "U6") (pin "18") (pinfunction "IO_18") (pintype "passive"))
    )
    (net (code "87") (name "unconnected-(U6-IO-Pad19)") (class "Default")
      (node (ref "U6") (pin "19") (pinfunction "IO_19") (pintype "passive"))
    )
    (net (code "88") (name "unconnected-(U6-IO-Pad20)") (class "Default")
      (node (ref "U6") (pin "20") (pinfunction "IO_20") (pintype "passive"))
    )
    (net (code "89") (name "unconnected-(U6-IO-Pad21)") (class "Default")
      (node (ref "U6") (pin "21") (pinfunction "IO_21") (pintype "passive"))
    )
    (net (code "90") (name "unconnected-(U6-IO-Pad22)") (class "Default")
      (node (ref "U6") (pin "22") (pinfunction "IO_22") (pintype "passive"))
    )
    (net (code "91") (name "unconnected-(U6-IO-Pad27)") (class "Default")
      (node (ref "U6") (pin "27") (pinfunction "IO_27") (pintype "passive"))
    )
    (net (code "92") (name "unconnected-(U6-IO-Pad42)") (class "Default")
      (node (ref "U6") (pin "42") (pinfunction "IO_42") (pintype "passive"))
    )
  )
)
